# BUCK_2025-06-15_05-23-50.net
KiCad netlist of a schematic drawn in EasyEDA Pro
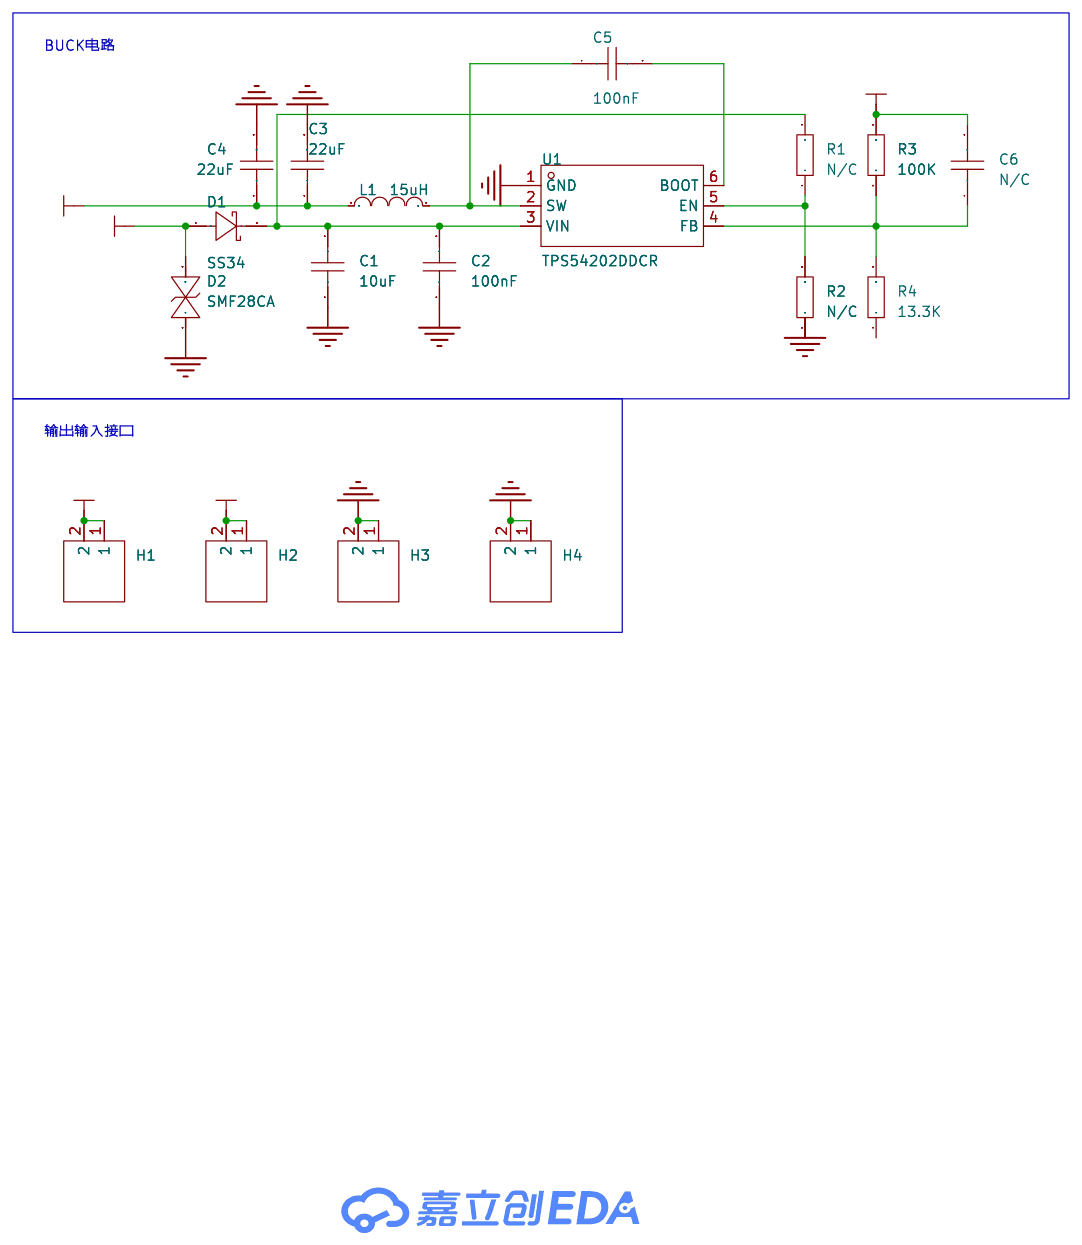
[diagram p0: schematic sheet]

(export (version "E")
  (design (tool "Eeschema 10.0.6"))
  (components
    (comp (ref "C1")
      (value "10uF")
      (footprint "easyedapro:C0805")
      (libsource (lib "easyedapro") (part "CapAcitance"))
    )
    (comp (ref "C2")
      (value "100nF")
      (footprint "easyedapro:C0805")
      (libsource (lib "easyedapro") (part "CapAcitance"))
    )
    (comp (ref "C3")
      (value "22uF")
      (footprint "easyedapro:C0805")
      (libsource (lib "easyedapro") (part "CapAcitance"))
    )
    (comp (ref "C4")
      (value "22uF")
      (footprint "easyedapro:C0805")
      (libsource (lib "easyedapro") (part "CapAcitance"))
    )
    (comp (ref "C5")
      (value "100nF")
      (footprint "easyedapro:C0805")
      (libsource (lib "easyedapro") (part "CapAcitance"))
    )
    (comp (ref "C6")
      (value "N/C")
      (footprint "easyedapro:C0805")
      (libsource (lib "easyedapro") (part "CapAcitance"))
    )
    (comp (ref "D1")
      (value "SS34")
      (footprint "easyedapro:SMA_L4.3-W2.6-LS5.0-FD")
      (description "二极管配置:独立式;正向压降(Vf):550mV@3.0A;直流反向耐压(Vr):40V;平均整流电流(Io):3A;")
      (fields (field (name "Manufacturer") "宏迦橙"))
      (libsource (lib "easyedapro") (part "SS34_C7420365"))
    )
    (comp (ref "D2")
      (value "SMF28CA")
      (footprint "easyedapro:SOD-123FL_L2.7-W1.8-LS3.8-BI")
      (fields (field (name "Manufacturer") "宏迦橙"))
      (libsource (lib "easyedapro") (part "SMF28CA_C19077517"))
    )
    (comp (ref "H1")
      (value "~")
      (footprint "easyedapro:HDR-TH_2P-P2.54-V-M-1")
      (libsource (lib "easyedapro") (part "210S-1*2P L=11.6MMGold-plated black"))
    )
    (comp (ref "H2")
      (value "~")
      (footprint "easyedapro:HDR-TH_2P-P2.54-V-M-1")
      (libsource (lib "easyedapro") (part "210S-1*2P L=11.6MMGold-plated black"))
    )
    (comp (ref "H3")
      (value "~")
      (footprint "easyedapro:HDR-TH_2P-P2.54-V-M-1")
      (libsource (lib "easyedapro") (part "210S-1*2P L=11.6MMGold-plated black"))
    )
    (comp (ref "H4")
      (value "~")
      (footprint "easyedapro:HDR-TH_2P-P2.54-V-M-1")
      (libsource (lib "easyedapro") (part "210S-1*2P L=11.6MMGold-plated black"))
    )
    (comp (ref "L1")
      (value "15uH")
      (footprint "easyedapro:IND-SMD_L7.0-W6.6_FXL0630")
      (description "电感值:15uH;精度:±20%;额定电流:3A;饱和电流(Isat):4.5A;类型:一体成型电感;")
      (fields (field (name "Manufacturer Part") "FXL0630-150-M") (field (name "Manufacturer") "cjiang(长江微电)"))
      (libsource (lib "easyedapro") (part "FXL0630-150-M"))
    )
    (comp (ref "R1") (value "N/C") (footprint "easyedapro:R0603") (libsource (lib "easyedapro") (part "电阻")))
    (comp (ref "R2") (value "N/C") (footprint "easyedapro:R0603") (libsource (lib "easyedapro") (part "电阻")))
    (comp (ref "R3") (value "100K") (footprint "easyedapro:R0603") (libsource (lib "easyedapro") (part "电阻")))
    (comp (ref "R4")
      (value "13.3K")
      (footprint "easyedapro:R0603")
      (libsource (lib "easyedapro") (part "电阻"))
    )
    (comp (ref "U1")
      (value "TPS54202DDCR")
      (footprint "easyedapro:SOT-23-6_L2.9-W1.6-P0.95-LS2.8-BL")
      (description "功能类型:降压型;输出类型:可调;工作电压:4.5V~28V;输出电压:-;输出电流:2A;")
      (fields (field (name "Manufacturer") "TI(德州仪器)"))
      (libsource (lib "easyedapro") (part "TPS54202DDCR"))
    )
  )
  (nets
    (net (code "1") (name "GND") (class "Default")
      (node (ref "C1") (pin "1") (pinfunction "1_1") (pintype "input"))
      (node (ref "C2") (pin "1") (pinfunction "1_1") (pintype "input"))
      (node (ref "C3") (pin "2") (pinfunction "2_2") (pintype "input"))
      (node (ref "C4") (pin "2") (pinfunction "2_2") (pintype "input"))
      (node (ref "D2") (pin "1") (pinfunction "1_1") (pintype "unspecified"))
      (node (ref "H3") (pin "1") (pinfunction "1_1") (pintype "unspecified"))
      (node (ref "H3") (pin "2") (pinfunction "2_2") (pintype "unspecified"))
      (node (ref "H4") (pin "1") (pinfunction "1_1") (pintype "unspecified"))
      (node (ref "H4") (pin "2") (pinfunction "2_2") (pintype "unspecified"))
      (node (ref "R2") (pin "1") (pinfunction "1_1") (pintype "input"))
      (node (ref "U1") (pin "1") (pinfunction "GND_1") (pintype "unspecified"))
    )
    (net (code "2") (name "Net-(D1-K)") (class "Default")
      (node (ref "C1") (pin "2") (pinfunction "2_2") (pintype "input"))
      (node (ref "C2") (pin "2") (pinfunction "2_2") (pintype "input"))
      (node (ref "D1") (pin "2") (pinfunction "K_2") (pintype "unspecified"))
      (node (ref "R1") (pin "2") (pinfunction "2_2") (pintype "input"))
      (node (ref "U1") (pin "3") (pinfunction "VIN_3") (pintype "unspecified"))
    )
    (net (code "3") (name "Net-(U1-BOOT)") (class "Default")
      (node (ref "C5") (pin "2") (pinfunction "2_2") (pintype "input"))
      (node (ref "U1") (pin "6") (pinfunction "BOOT_6") (pintype "unspecified"))
    )
    (net (code "4") (name "Net-(U1-EN)") (class "Default")
      (node (ref "R1") (pin "1") (pinfunction "1_1") (pintype "input"))
      (node (ref "R2") (pin "2") (pinfunction "2_2") (pintype "input"))
      (node (ref "U1") (pin "5") (pinfunction "EN_5") (pintype "unspecified"))
    )
    (net (code "5") (name "Net-(U1-FB)") (class "Default")
      (node (ref "C6") (pin "1") (pinfunction "1_1") (pintype "input"))
      (node (ref "R3") (pin "1") (pinfunction "1_1") (pintype "input"))
      (node (ref "R4") (pin "2") (pinfunction "2_2") (pintype "input"))
      (node (ref "U1") (pin "4") (pinfunction "FB_4") (pintype "unspecified"))
    )
    (net (code "6") (name "Net-(U1-SW)") (class "Default")
      (node (ref "C5") (pin "1") (pinfunction "1_1") (pintype "input"))
      (node (ref "L1") (pin "2") (pinfunction "2_2") (pintype "unspecified"))
      (node (ref "U1") (pin "2") (pinfunction "SW_2") (pintype "unspecified"))
    )
    (net (code "7") (name "VIN") (class "Default")
      (node (ref "D1") (pin "1") (pinfunction "A_1") (pintype "unspecified"))
      (node (ref "D2") (pin "2") (pinfunction "2_2") (pintype "unspecified"))
      (node (ref "H1") (pin "1") (pinfunction "1_1") (pintype "unspecified"))
      (node (ref "H1") (pin "2") (pinfunction "2_2") (pintype "unspecified"))
    )
    (net (code "8") (name "VOUT") (class "Default")
      (node (ref "C3") (pin "1") (pinfunction "1_1") (pintype "input"))
      (node (ref "C4") (pin "1") (pinfunction "1_1") (pintype "input"))
      (node (ref "C6") (pin "2") (pinfunction "2_2") (pintype "input"))
      (node (ref "H2") (pin "1") (pinfunction "1_1") (pintype "unspecified"))
      (node (ref "H2") (pin "2") (pinfunction "2_2") (pintype "unspecified"))
      (node (ref "L1") (pin "1") (pinfunction "1_1") (pintype "unspecified"))
      (node (ref "R3") (pin "2") (pinfunction "2_2") (pintype "input"))
    )
    (net (code "9") (name "unconnected-(R4-Pad1)") (class "Default")
      (node (ref "R4") (pin "1") (pinfunction "1_1") (pintype "input"))
    )
  )
)
